# kuzgunfe_fc0_2.net
KiCad netlist of a schematic drawn in Altium Designer
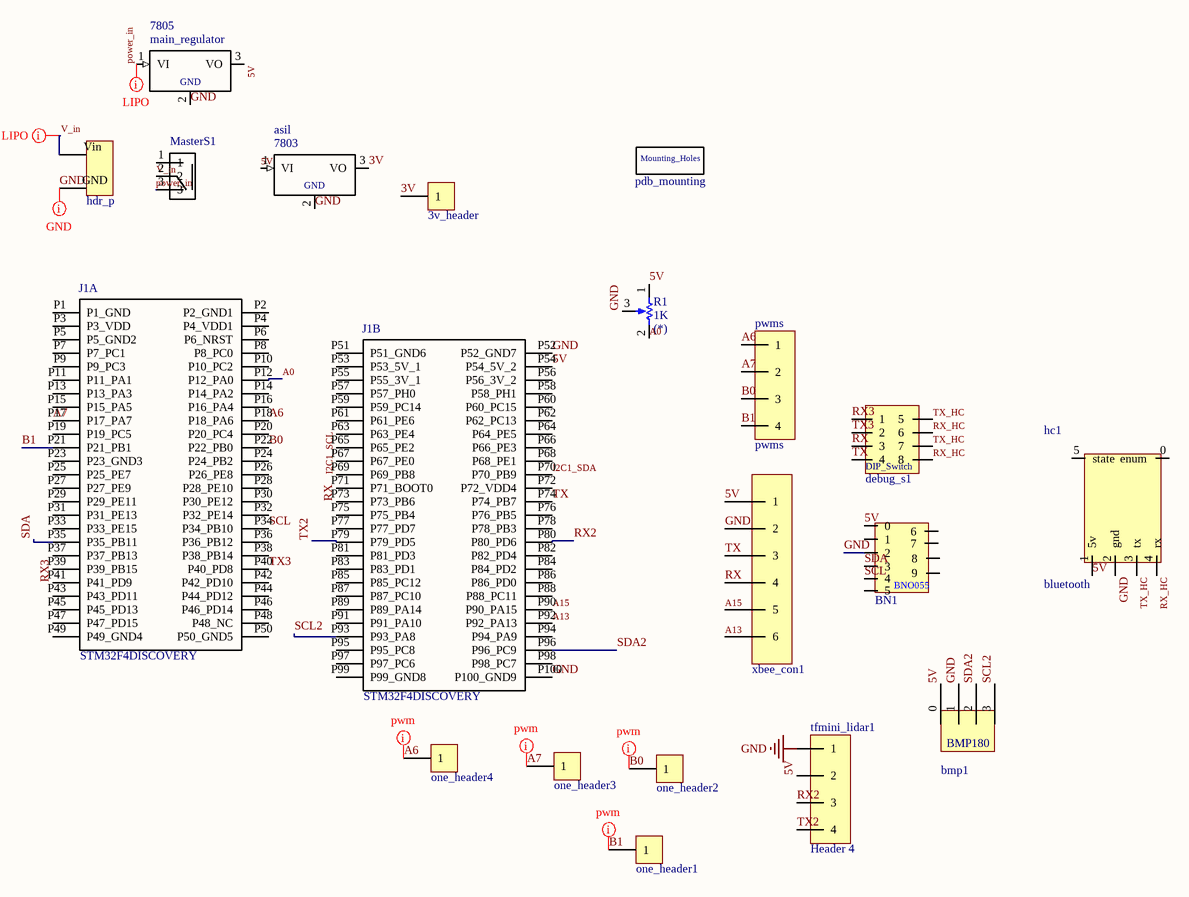
[diagram p0: kuzgunfe_fc0.2.SchDoc]

(export (version "E")
  (design (tool "Eeschema 10.0.6"))
  (components
    (comp (ref "3v_header")
      (value "3v_header")
      (footprint "tekli_header")
      (libsource (lib "headers") (part "one_header"))
    )
    (comp (ref "7805")
      (value "main_regulator")
      (footprint "TO92-")
      (description "Conn Quick Fit Header HDR 5 POS 5.1mm Solder RA Thru-Hole")
      (fields (field (name "MF") "Keystone") (field (name "MP") "7805"))
      (libsource (lib "7805") (part "7805"))
    )
    (comp (ref "asil")
      (value "7803")
      (footprint "TO92-")
      (description "Conn Quick Fit Header HDR 5 POS 5.1mm Solder RA Thru-Hole")
      (fields (field (name "MF") "Keystone") (field (name "MP") "7805"))
      (libsource (lib "7805") (part "7805"))
    )
    (comp (ref "bmp1") (value "bmp") (footprint "bmp") (libsource (lib "bmp180") (part "bmp")))
    (comp (ref "BN1") (value "BNO055") (footprint "bno055") (libsource (lib "bno055") (part "BNO055")))
    (comp (ref "debug_s1")
      (value "dipswitch")
      (footprint "JUMPER4_PIN")
      (libsource (lib "dipswitch") (part "dipswitch"))
    )
    (comp (ref "hc1")
      (value "bluetooth")
      (footprint "hc05")
      (description "bluetooth device hc 05")
      (libsource (lib "hc05") (part "hc05"))
    )
    (comp (ref "hdr_p")
      (value "header_2_power")
      (footprint "HDR2_POWER")
      (libsource (lib "headers") (part "header_2_power"))
    )
    (comp (ref "J1")
      (value "STM32F4DISCOVERY")
      (footprint "STMICROELECTRONICS_STM32F4DISCOVERY_STM32F4DISCOVERY(Primary)")
      (description "Development kit: ARM ST; pin strips, pin header; No.of")
      (fields (field (name "MF") "STMicroelectronics"))
      (libsource (lib "STM32F4DISCOVERY") (part "STM32F4DISCOVERY"))
    )
    (comp (ref "MasterS1")
      (value "Master_S")
      (footprint "SW")
      (description "Switch Slide ON ON SPDT Top Slide 0.1A 12VDC 10000Cycles PC Pins Thru-Hole Bulk")
      (fields (field (name "MF") "C&K Components"))
      (libsource (lib "slide_switch") (part "Master_S"))
    )
    (comp (ref "one_header1")
      (value "one_header")
      (footprint "tekli_header")
      (libsource (lib "headers") (part "one_header"))
    )
    (comp (ref "one_header2")
      (value "one_header")
      (footprint "tekli_header")
      (libsource (lib "headers") (part "one_header"))
    )
    (comp (ref "one_header3")
      (value "one_header")
      (footprint "tekli_header")
      (libsource (lib "headers") (part "one_header"))
    )
    (comp (ref "one_header4")
      (value "one_header")
      (footprint "tekli_header")
      (libsource (lib "headers") (part "one_header"))
    )
    (comp (ref "pdb_mounting")
      (value "pdb_mounting")
      (footprint "pdb_mounting_v1")
      (libsource (lib "mounting_holes") (part "pdb_mounting"))
    )
    (comp (ref "pwms") (value "pwms") (footprint "HDR4_pin") (libsource (lib "headers") (part "Header 4")))
    (comp (ref "R1")
      (value "1K")
      (footprint "pot_alpha")
      (description "Potentiometer")
      (fields
        (field (name "TYPE") "(*)")
        (field (name "Comment") "ALPHA Potentiometer")
        (field (name "PUBLISHER") "Altium Limited")
      )
      (libsource (lib "potentiometers") (part "alpha-pot"))
    )
    (comp (ref "tfmini_lidar1")
      (value "Header 4")
      (footprint "HDR4_pin")
      (libsource (lib "headers") (part "Header 4"))
    )
    (comp (ref "xbee_con1")
      (value "header_6")
      (footprint "hdr_6pın")
      (libsource (lib "headers") (part "header_6"))
    )
  )
  (nets
    (net (code "1") (name "/3V") (class "Default")
      (node (ref "3v_header") (pin "1") (pinfunction "1_1") (pintype "passive"))
      (node (ref "asil") (pin "3") (pinfunction "VO_3") (pintype "passive"))
    )
    (net (code "2") (name "/5V") (class "Default")
      (node (ref "7805") (pin "3") (pinfunction "VO_3") (pintype "passive"))
      (node (ref "BN1") (pin "0") (pinfunction "0_0") (pintype "passive"))
      (node (ref "J1") (pin "P54") (pinfunction "P54_5V_2_P54") (pintype "passive"))
      (node (ref "R1") (pin "1") (pinfunction "TOP_1") (pintype "passive"))
      (node (ref "asil") (pin "1") (pinfunction "VI_1") (pintype "input"))
      (node (ref "bmp1") (pin "0") (pinfunction "0_0") (pintype "passive"))
      (node (ref "hc1") (pin "1") (pinfunction "5v_1") (pintype "passive"))
      (node (ref "tfmini_lidar1") (pin "2") (pinfunction "2_2") (pintype "passive"))
      (node (ref "xbee_con1") (pin "1") (pinfunction "1_1") (pintype "passive"))
    )
    (net (code "3") (name "/A0") (class "Default")
      (node (ref "J1") (pin "P12") (pinfunction "P12_PA0_P12") (pintype "passive"))
      (node (ref "R1") (pin "2") (pinfunction "BOT_2") (pintype "passive"))
    )
    (net (code "4") (name "/A6") (class "Default")
      (node (ref "J1") (pin "P18") (pinfunction "P18_PA6_P18") (pintype "passive"))
      (node (ref "one_header4") (pin "1") (pinfunction "1_1") (pintype "passive"))
      (node (ref "pwms") (pin "1") (pinfunction "1_1") (pintype "passive"))
    )
    (net (code "5") (name "/A7") (class "Default")
      (node (ref "J1") (pin "P17") (pinfunction "P17_PA7_P17") (pintype "passive"))
      (node (ref "one_header3") (pin "1") (pinfunction "1_1") (pintype "passive"))
      (node (ref "pwms") (pin "2") (pinfunction "2_2") (pintype "passive"))
    )
    (net (code "6") (name "/A13") (class "Default")
      (node (ref "J1") (pin "P92") (pinfunction "P92_PA13_P92") (pintype "passive"))
      (node (ref "xbee_con1") (pin "6") (pinfunction "6_6") (pintype "passive"))
    )
    (net (code "7") (name "/A15") (class "Default")
      (node (ref "J1") (pin "P90") (pinfunction "P90_PA15_P90") (pintype "passive"))
      (node (ref "xbee_con1") (pin "5") (pinfunction "5_5") (pintype "passive"))
    )
    (net (code "8") (name "/B0") (class "Default")
      (node (ref "J1") (pin "P22") (pinfunction "P22_PB0_P22") (pintype "passive"))
      (node (ref "one_header2") (pin "1") (pinfunction "1_1") (pintype "passive"))
      (node (ref "pwms") (pin "3") (pinfunction "3_3") (pintype "passive"))
    )
    (net (code "9") (name "/B1") (class "Default")
      (node (ref "J1") (pin "P21") (pinfunction "P21_PB1_P21") (pintype "passive"))
      (node (ref "one_header1") (pin "1") (pinfunction "1_1") (pintype "passive"))
      (node (ref "pwms") (pin "4") (pinfunction "4_4") (pintype "passive"))
    )
    (net (code "10") (name "/I2C1_SCL") (class "Default")
      (node (ref "J1") (pin "P69") (pinfunction "P69_PB8_P69") (pintype "passive"))
    )
    (net (code "11") (name "/I2C1_SDA") (class "Default")
      (node (ref "J1") (pin "P70") (pinfunction "P70_PB9_P70") (pintype "passive"))
    )
    (net (code "12") (name "/RX") (class "Default")
      (node (ref "J1") (pin "P73") (pinfunction "P73_PB6_P73") (pintype "passive"))
      (node (ref "debug_s1") (pin "3") (pinfunction "3_3") (pintype "passive"))
      (node (ref "xbee_con1") (pin "4") (pinfunction "4_4") (pintype "passive"))
    )
    (net (code "13") (name "/RX2") (class "Default")
      (node (ref "J1") (pin "P80") (pinfunction "P80_PD6_P80") (pintype "passive"))
      (node (ref "tfmini_lidar1") (pin "3") (pinfunction "3_3") (pintype "passive"))
    )
    (net (code "14") (name "/RX3") (class "Default")
      (node (ref "J1") (pin "P41") (pinfunction "P41_PD9_P41") (pintype "passive"))
      (node (ref "debug_s1") (pin "1") (pinfunction "1_1") (pintype "passive"))
    )
    (net (code "15") (name "/RX_HC") (class "Default")
      (node (ref "debug_s1") (pin "6") (pinfunction "6_6") (pintype "passive"))
      (node (ref "debug_s1") (pin "8") (pinfunction "8_8") (pintype "passive"))
      (node (ref "hc1") (pin "4") (pinfunction "rx_4") (pintype "passive"))
    )
    (net (code "16") (name "/SCL") (class "Default")
      (node (ref "BN1") (pin "4") (pinfunction "4_4") (pintype "passive"))
      (node (ref "J1") (pin "P34") (pinfunction "P34_PB10_P34") (pintype "passive"))
    )
    (net (code "17") (name "/SCL2") (class "Default")
      (node (ref "J1") (pin "P93") (pinfunction "P93_PA8_P93") (pintype "passive"))
      (node (ref "bmp1") (pin "3") (pinfunction "3_3") (pintype "passive"))
    )
    (net (code "18") (name "/SDA") (class "Default")
      (node (ref "BN1") (pin "3") (pinfunction "3_3") (pintype "passive"))
      (node (ref "J1") (pin "P35") (pinfunction "P35_PB11_P35") (pintype "passive"))
    )
    (net (code "19") (name "/SDA2") (class "Default")
      (node (ref "J1") (pin "P96") (pinfunction "P96_PC9_P96") (pintype "passive"))
      (node (ref "bmp1") (pin "2") (pinfunction "2_2") (pintype "passive"))
    )
    (net (code "20") (name "/TX") (class "Default")
      (node (ref "J1") (pin "P74") (pinfunction "P74_PB7_P74") (pintype "passive"))
      (node (ref "debug_s1") (pin "4") (pinfunction "4_4") (pintype "passive"))
      (node (ref "xbee_con1") (pin "3") (pinfunction "3_3") (pintype "passive"))
    )
    (net (code "21") (name "/TX2") (class "Default")
      (node (ref "J1") (pin "P79") (pinfunction "P79_PD5_P79") (pintype "passive"))
      (node (ref "tfmini_lidar1") (pin "4") (pinfunction "4_4") (pintype "passive"))
    )
    (net (code "22") (name "/TX3") (class "Default")
      (node (ref "J1") (pin "P40") (pinfunction "P40_PD8_P40") (pintype "passive"))
      (node (ref "debug_s1") (pin "2") (pinfunction "2_2") (pintype "passive"))
    )
    (net (code "23") (name "/TX_HC") (class "Default")
      (node (ref "debug_s1") (pin "5") (pinfunction "5_5") (pintype "passive"))
      (node (ref "debug_s1") (pin "7") (pinfunction "7_7") (pintype "passive"))
      (node (ref "hc1") (pin "3") (pinfunction "tx_3") (pintype "passive"))
    )
    (net (code "24") (name "/V_in") (class "Default")
      (node (ref "MasterS1") (pin "2") (pinfunction "2_2") (pintype "passive"))
      (node (ref "hdr_p") (pin "Vin") (pinfunction "1_Vin") (pintype "passive"))
    )
    (net (code "25") (name "/power_in") (class "Default")
      (node (ref "7805") (pin "1") (pinfunction "VI_1") (pintype "input"))
      (node (ref "MasterS1") (pin "3") (pinfunction "3_3") (pintype "passive"))
    )
    (net (code "26") (name "GND") (class "Default")
      (node (ref "7805") (pin "2") (pinfunction "GND_2") (pintype "passive"))
      (node (ref "BN1") (pin "2") (pinfunction "2_2") (pintype "passive"))
      (node (ref "J1") (pin "P100") (pinfunction "P100_GND9_P100") (pintype "passive"))
      (node (ref "J1") (pin "P52") (pinfunction "P52_GND7_P52") (pintype "passive"))
      (node (ref "R1") (pin "3") (pinfunction "TAP_3") (pintype "passive"))
      (node (ref "asil") (pin "2") (pinfunction "GND_2") (pintype "passive"))
      (node (ref "bmp1") (pin "1") (pinfunction "1_1") (pintype "passive"))
      (node (ref "hc1") (pin "2") (pinfunction "gnd_2") (pintype "passive"))
      (node (ref "hdr_p") (pin "GND") (pinfunction "2_GND") (pintype "passive"))
      (node (ref "tfmini_lidar1") (pin "1") (pinfunction "1_1") (pintype "passive"))
      (node (ref "xbee_con1") (pin "2") (pinfunction "2_2") (pintype "passive"))
    )
    (net (code "27") (name "unconnected-(BN1-Pad1)") (class "Default")
      (node (ref "BN1") (pin "1") (pinfunction "1_1") (pintype "passive"))
    )
    (net (code "28") (name "unconnected-(BN1-Pad5)") (class "Default")
      (node (ref "BN1") (pin "5") (pinfunction "5_5") (pintype "passive"))
    )
    (net (code "29") (name "unconnected-(BN1-Pad6)") (class "Default")
      (node (ref "BN1") (pin "6") (pinfunction "6_6") (pintype "passive"))
    )
    (net (code "30") (name "unconnected-(BN1-Pad7)") (class "Default")
      (node (ref "BN1") (pin "7") (pinfunction "7_7") (pintype "passive"))
    )
    (net (code "31") (name "unconnected-(BN1-Pad8)") (class "Default")
      (node (ref "BN1") (pin "8") (pinfunction "8_8") (pintype "passive"))
    )
    (net (code "32") (name "unconnected-(BN1-Pad9)") (class "Default")
      (node (ref "BN1") (pin "9") (pinfunction "9_9") (pintype "passive"))
    )
    (net (code "33") (name "unconnected-(J1A-P1_GND-PadP1)") (class "Default")
      (node (ref "J1") (pin "P1") (pinfunction "P1_GND_P1") (pintype "passive"))
    )
    (net (code "34") (name "unconnected-(J1A-P2_GND1-PadP2)") (class "Default")
      (node (ref "J1") (pin "P2") (pinfunction "P2_GND1_P2") (pintype "passive"))
    )
    (net (code "35") (name "unconnected-(J1A-P3_VDD-PadP3)") (class "Default")
      (node (ref "J1") (pin "P3") (pinfunction "P3_VDD_P3") (pintype "passive"))
    )
    (net (code "36") (name "unconnected-(J1A-P4_VDD1-PadP4)") (class "Default")
      (node (ref "J1") (pin "P4") (pinfunction "P4_VDD1_P4") (pintype "passive"))
    )
    (net (code "37") (name "unconnected-(J1A-P5_GND2-PadP5)") (class "Default")
      (node (ref "J1") (pin "P5") (pinfunction "P5_GND2_P5") (pintype "passive"))
    )
    (net (code "38") (name "unconnected-(J1A-P6_NRST-PadP6)") (class "Default")
      (node (ref "J1") (pin "P6") (pinfunction "P6_NRST_P6") (pintype "passive"))
    )
    (net (code "39") (name "unconnected-(J1A-P7_PC1-PadP7)") (class "Default")
      (node (ref "J1") (pin "P7") (pinfunction "P7_PC1_P7") (pintype "passive"))
    )
    (net (code "40") (name "unconnected-(J1A-P8_PC0-PadP8)") (class "Default")
      (node (ref "J1") (pin "P8") (pinfunction "P8_PC0_P8") (pintype "passive"))
    )
    (net (code "41") (name "unconnected-(J1A-P9_PC3-PadP9)") (class "Default")
      (node (ref "J1") (pin "P9") (pinfunction "P9_PC3_P9") (pintype "passive"))
    )
    (net (code "42") (name "unconnected-(J1A-P10_PC2-PadP10)") (class "Default")
      (node (ref "J1") (pin "P10") (pinfunction "P10_PC2_P10") (pintype "passive"))
    )
    (net (code "43") (name "unconnected-(J1A-P11_PA1-PadP11)") (class "Default")
      (node (ref "J1") (pin "P11") (pinfunction "P11_PA1_P11") (pintype "passive"))
    )
    (net (code "44") (name "unconnected-(J1A-P13_PA3-PadP13)") (class "Default")
      (node (ref "J1") (pin "P13") (pinfunction "P13_PA3_P13") (pintype "passive"))
    )
    (net (code "45") (name "unconnected-(J1A-P14_PA2-PadP14)") (class "Default")
      (node (ref "J1") (pin "P14") (pinfunction "P14_PA2_P14") (pintype "passive"))
    )
    (net (code "46") (name "unconnected-(J1A-P15_PA5-PadP15)") (class "Default")
      (node (ref "J1") (pin "P15") (pinfunction "P15_PA5_P15") (pintype "passive"))
    )
    (net (code "47") (name "unconnected-(J1A-P16_PA4-PadP16)") (class "Default")
      (node (ref "J1") (pin "P16") (pinfunction "P16_PA4_P16") (pintype "passive"))
    )
    (net (code "48") (name "unconnected-(J1A-P19_PC5-PadP19)") (class "Default")
      (node (ref "J1") (pin "P19") (pinfunction "P19_PC5_P19") (pintype "passive"))
    )
    (net (code "49") (name "unconnected-(J1A-P20_PC4-PadP20)") (class "Default")
      (node (ref "J1") (pin "P20") (pinfunction "P20_PC4_P20") (pintype "passive"))
    )
    (net (code "50") (name "unconnected-(J1A-P23_GND3-PadP23)") (class "Default")
      (node (ref "J1") (pin "P23") (pinfunction "P23_GND3_P23") (pintype "passive"))
    )
    (net (code "51") (name "unconnected-(J1A-P24_PB2-PadP24)") (class "Default")
      (node (ref "J1") (pin "P24") (pinfunction "P24_PB2_P24") (pintype "passive"))
    )
    (net (code "52") (name "unconnected-(J1A-P25_PE7-PadP25)") (class "Default")
      (node (ref "J1") (pin "P25") (pinfunction "P25_PE7_P25") (pintype "passive"))
    )
    (net (code "53") (name "unconnected-(J1A-P26_PE8-PadP26)") (class "Default")
      (node (ref "J1") (pin "P26") (pinfunction "P26_PE8_P26") (pintype "passive"))
    )
    (net (code "54") (name "unconnected-(J1A-P27_PE9-PadP27)") (class "Default")
      (node (ref "J1") (pin "P27") (pinfunction "P27_PE9_P27") (pintype "passive"))
    )
    (net (code "55") (name "unconnected-(J1A-P28_PE10-PadP28)") (class "Default")
      (node (ref "J1") (pin "P28") (pinfunction "P28_PE10_P28") (pintype "passive"))
    )
    (net (code "56") (name "unconnected-(J1A-P29_PE11-PadP29)") (class "Default")
      (node (ref "J1") (pin "P29") (pinfunction "P29_PE11_P29") (pintype "passive"))
    )
    (net (code "57") (name "unconnected-(J1A-P30_PE12-PadP30)") (class "Default")
      (node (ref "J1") (pin "P30") (pinfunction "P30_PE12_P30") (pintype "passive"))
    )
    (net (code "58") (name "unconnected-(J1A-P31_PE13-PadP31)") (class "Default")
      (node (ref "J1") (pin "P31") (pinfunction "P31_PE13_P31") (pintype "passive"))
    )
    (net (code "59") (name "unconnected-(J1A-P32_PE14-PadP32)") (class "Default")
      (node (ref "J1") (pin "P32") (pinfunction "P32_PE14_P32") (pintype "passive"))
    )
    (net (code "60") (name "unconnected-(J1A-P33_PE15-PadP33)") (class "Default")
      (node (ref "J1") (pin "P33") (pinfunction "P33_PE15_P33") (pintype "passive"))
    )
    (net (code "61") (name "unconnected-(J1A-P36_PB12-PadP36)") (class "Default")
      (node (ref "J1") (pin "P36") (pinfunction "P36_PB12_P36") (pintype "passive"))
    )
    (net (code "62") (name "unconnected-(J1A-P37_PB13-PadP37)") (class "Default")
      (node (ref "J1") (pin "P37") (pinfunction "P37_PB13_P37") (pintype "passive"))
    )
    (net (code "63") (name "unconnected-(J1A-P38_PB14-PadP38)") (class "Default")
      (node (ref "J1") (pin "P38") (pinfunction "P38_PB14_P38") (pintype "passive"))
    )
    (net (code "64") (name "unconnected-(J1A-P39_PB15-PadP39)") (class "Default")
      (node (ref "J1") (pin "P39") (pinfunction "P39_PB15_P39") (pintype "passive"))
    )
    (net (code "65") (name "unconnected-(J1A-P42_PD10-PadP42)") (class "Default")
      (node (ref "J1") (pin "P42") (pinfunction "P42_PD10_P42") (pintype "passive"))
    )
    (net (code "66") (name "unconnected-(J1A-P43_PD11-PadP43)") (class "Default")
      (node (ref "J1") (pin "P43") (pinfunction "P43_PD11_P43") (pintype "passive"))
    )
    (net (code "67") (name "unconnected-(J1A-P44_PD12-PadP44)") (class "Default")
      (node (ref "J1") (pin "P44") (pinfunction "P44_PD12_P44") (pintype "passive"))
    )
    (net (code "68") (name "unconnected-(J1A-P45_PD13-PadP45)") (class "Default")
      (node (ref "J1") (pin "P45") (pinfunction "P45_PD13_P45") (pintype "passive"))
    )
    (net (code "69") (name "unconnected-(J1A-P46_PD14-PadP46)") (class "Default")
      (node (ref "J1") (pin "P46") (pinfunction "P46_PD14_P46") (pintype "passive"))
    )
    (net (code "70") (name "unconnected-(J1A-P47_PD15-PadP47)") (class "Default")
      (node (ref "J1") (pin "P47") (pinfunction "P47_PD15_P47") (pintype "passive"))
    )
    (net (code "71") (name "unconnected-(J1A-P48_NC-PadP48)") (class "Default")
      (node (ref "J1") (pin "P48") (pinfunction "P48_NC_P48") (pintype "passive"))
    )
    (net (code "72") (name "unconnected-(J1A-P49_GND4-PadP49)") (class "Default")
      (node (ref "J1") (pin "P49") (pinfunction "P49_GND4_P49") (pintype "passive"))
    )
    (net (code "73") (name "unconnected-(J1A-P50_GND5-PadP50)") (class "Default")
      (node (ref "J1") (pin "P50") (pinfunction "P50_GND5_P50") (pintype "passive"))
    )
    (net (code "74") (name "unconnected-(J1B-P51_GND6-PadP51)") (class "Default")
      (node (ref "J1") (pin "P51") (pinfunction "P51_GND6_P51") (pintype "passive"))
    )
    (net (code "75") (name "unconnected-(J1B-P53_5V_1-PadP53)") (class "Default")
      (node (ref "J1") (pin "P53") (pinfunction "P53_5V_1_P53") (pintype "passive"))
    )
    (net (code "76") (name "unconnected-(J1B-P55_3V_1-PadP55)") (class "Default")
      (node (ref "J1") (pin "P55") (pinfunction "P55_3V_1_P55") (pintype "passive"))
    )
    (net (code "77") (name "unconnected-(J1B-P56_3V_2-PadP56)") (class "Default")
      (node (ref "J1") (pin "P56") (pinfunction "P56_3V_2_P56") (pintype "passive"))
    )
    (net (code "78") (name "unconnected-(J1B-P57_PH0-PadP57)") (class "Default")
      (node (ref "J1") (pin "P57") (pinfunction "P57_PH0_P57") (pintype "passive"))
    )
    (net (code "79") (name "unconnected-(J1B-P58_PH1-PadP58)") (class "Default")
      (node (ref "J1") (pin "P58") (pinfunction "P58_PH1_P58") (pintype "passive"))
    )
    (net (code "80") (name "unconnected-(J1B-P59_PC14-PadP59)") (class "Default")
      (node (ref "J1") (pin "P59") (pinfunction "P59_PC14_P59") (pintype "passive"))
    )
    (net (code "81") (name "unconnected-(J1B-P60_PC15-PadP60)") (class "Default")
      (node (ref "J1") (pin "P60") (pinfunction "P60_PC15_P60") (pintype "passive"))
    )
    (net (code "82") (name "unconnected-(J1B-P61_PE6-PadP61)") (class "Default")
      (node (ref "J1") (pin "P61") (pinfunction "P61_PE6_P61") (pintype "passive"))
    )
    (net (code "83") (name "unconnected-(J1B-P62_PC13-PadP62)") (class "Default")
      (node (ref "J1") (pin "P62") (pinfunction "P62_PC13_P62") (pintype "passive"))
    )
    (net (code "84") (name "unconnected-(J1B-P63_PE4-PadP63)") (class "Default")
      (node (ref "J1") (pin "P63") (pinfunction "P63_PE4_P63") (pintype "passive"))
    )
    (net (code "85") (name "unconnected-(J1B-P64_PE5-PadP64)") (class "Default")
      (node (ref "J1") (pin "P64") (pinfunction "P64_PE5_P64") (pintype "passive"))
    )
    (net (code "86") (name "unconnected-(J1B-P65_PE2-PadP65)") (class "Default")
      (node (ref "J1") (pin "P65") (pinfunction "P65_PE2_P65") (pintype "passive"))
    )
    (net (code "87") (name "unconnected-(J1B-P66_PE3-PadP66)") (class "Default")
      (node (ref "J1") (pin "P66") (pinfunction "P66_PE3_P66") (pintype "passive"))
    )
    (net (code "88") (name "unconnected-(J1B-P67_PE0-PadP67)") (class "Default")
      (node (ref "J1") (pin "P67") (pinfunction "P67_PE0_P67") (pintype "passive"))
    )
    (net (code "89") (name "unconnected-(J1B-P68_PE1-PadP68)") (class "Default")
      (node (ref "J1") (pin "P68") (pinfunction "P68_PE1_P68") (pintype "passive"))
    )
    (net (code "90") (name "unconnected-(J1B-P71_BOOT0-PadP71)") (class "Default")
      (node (ref "J1") (pin "P71") (pinfunction "P71_BOOT0_P71") (pintype "passive"))
    )
    (net (code "91") (name "unconnected-(J1B-P72_VDD4-PadP72)") (class "Default")
      (node (ref "J1") (pin "P72") (pinfunction "P72_VDD4_P72") (pintype "passive"))
    )
    (net (code "92") (name "unconnected-(J1B-P75_PB4-PadP75)") (class "Default")
      (node (ref "J1") (pin "P75") (pinfunction "P75_PB4_P75") (pintype "passive"))
    )
    (net (code "93") (name "unconnected-(J1B-P76_PB5-PadP76)") (class "Default")
      (node (ref "J1") (pin "P76") (pinfunction "P76_PB5_P76") (pintype "passive"))
    )
    (net (code "94") (name "unconnected-(J1B-P77_PD7-PadP77)") (class "Default")
      (node (ref "J1") (pin "P77") (pinfunction "P77_PD7_P77") (pintype "passive"))
    )
    (net (code "95") (name "unconnected-(J1B-P78_PB3-PadP78)") (class "Default")
      (node (ref "J1") (pin "P78") (pinfunction "P78_PB3_P78") (pintype "passive"))
    )
    (net (code "96") (name "unconnected-(J1B-P81_PD3-PadP81)") (class "Default")
      (node (ref "J1") (pin "P81") (pinfunction "P81_PD3_P81") (pintype "passive"))
    )
    (net (code "97") (name "unconnected-(J1B-P82_PD4-PadP82)") (class "Default")
      (node (ref "J1") (pin "P82") (pinfunction "P82_PD4_P82") (pintype "passive"))
    )
    (net (code "98") (name "unconnected-(J1B-P83_PD1-PadP83)") (class "Default")
      (node (ref "J1") (pin "P83") (pinfunction "P83_PD1_P83") (pintype "passive"))
    )
    (net (code "99") (name "unconnected-(J1B-P84_PD2-PadP84)") (class "Default")
      (node (ref "J1") (pin "P84") (pinfunction "P84_PD2_P84") (pintype "passive"))
    )
    (net (code "100") (name "unconnected-(J1B-P85_PC12-PadP85)") (class "Default")
      (node (ref "J1") (pin "P85") (pinfunction "P85_PC12_P85") (pintype "passive"))
    )
    (net (code "101") (name "unconnected-(J1B-P86_PD0-PadP86)") (class "Default")
      (node (ref "J1") (pin "P86") (pinfunction "P86_PD0_P86") (pintype "passive"))
    )
    (net (code "102") (name "unconnected-(J1B-P87_PC10-PadP87)") (class "Default")
      (node (ref "J1") (pin "P87") (pinfunction "P87_PC10_P87") (pintype "passive"))
    )
    (net (code "103") (name "unconnected-(J1B-P88_PC11-PadP88)") (class "Default")
      (node (ref "J1") (pin "P88") (pinfunction "P88_PC11_P88") (pintype "passive"))
    )
    (net (code "104") (name "unconnected-(J1B-P89_PA14-PadP89)") (class "Default")
      (node (ref "J1") (pin "P89") (pinfunction "P89_PA14_P89") (pintype "passive"))
    )
    (net (code "105") (name "unconnected-(J1B-P91_PA10-PadP91)") (class "Default")
      (node (ref "J1") (pin "P91") (pinfunction "P91_PA10_P91") (pintype "passive"))
    )
    (net (code "106") (name "unconnected-(J1B-P94_PA9-PadP94)") (class "Default")
      (node (ref "J1") (pin "P94") (pinfunction "P94_PA9_P94") (pintype "passive"))
    )
    (net (code "107") (name "unconnected-(J1B-P95_PC8-PadP95)") (class "Default")
      (node (ref "J1") (pin "P95") (pinfunction "P95_PC8_P95") (pintype "passive"))
    )
    (net (code "108") (name "unconnected-(J1B-P97_PC6-PadP97)") (class "Default")
      (node (ref "J1") (pin "P97") (pinfunction "P97_PC6_P97") (pintype "passive"))
    )
    (net (code "109") (name "unconnected-(J1B-P98_PC7-PadP98)") (class "Default")
      (node (ref "J1") (pin "P98") (pinfunction "P98_PC7_P98") (pintype "passive"))
    )
    (net (code "110") (name "unconnected-(J1B-P99_GND8-PadP99)") (class "Default")
      (node (ref "J1") (pin "P99") (pinfunction "P99_GND8_P99") (pintype "passive"))
    )
    (net (code "111") (name "unconnected-(MasterS1-Pad1)") (class "Default")
      (node (ref "MasterS1") (pin "1") (pinfunction "1_1") (pintype "passive"))
    )
    (net (code "112") (name "unconnected-(hc1-enum-Pad0)") (class "Default")
      (node (ref "hc1") (pin "0") (pinfunction "enum_0") (pintype "passive"))
    )
    (net (code "113") (name "unconnected-(hc1-state-Pad5)") (class "Default")
      (node (ref "hc1") (pin "5") (pinfunction "state_5") (pintype "passive"))
    )
  )
)
